# CH32F103C-R0.net
KiCad netlist of a schematic drawn in Altium Designer
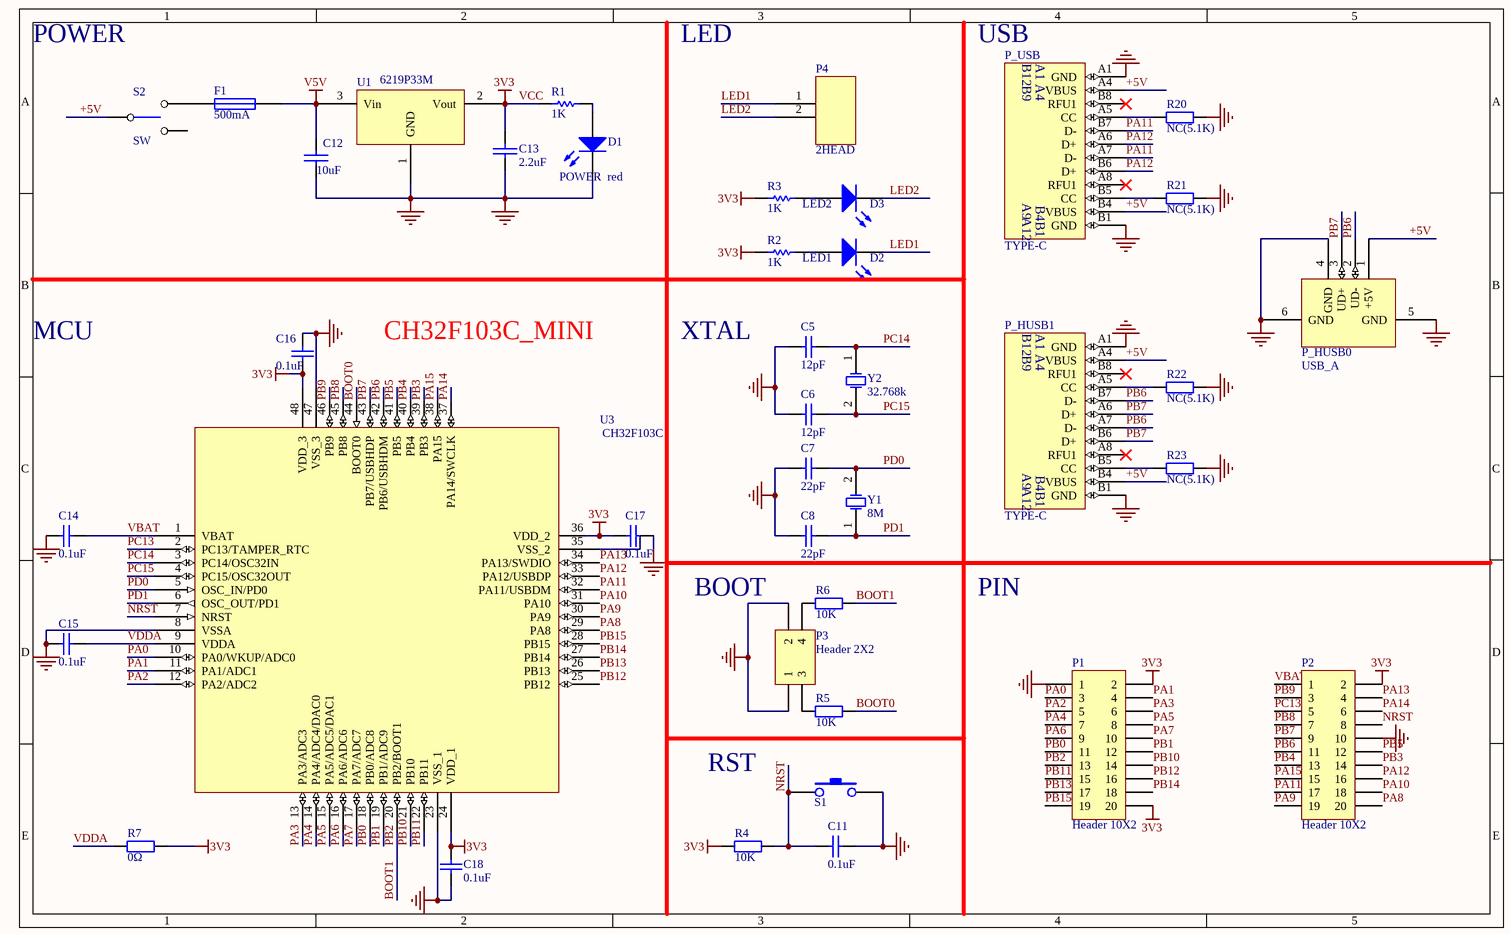
[diagram p0: CH32F103C-R0.SchDoc]

(export (version "E")
  (design (tool "Eeschema 10.0.6"))
  (components
    (comp (ref "C5")
      (value "12pF")
      (footprint "0603")
      (description "Capacitor")
      (fields (field (name "PUBLISHER") "Altium Limited"))
      (libsource (lib "*") (part "Cap"))
    )
    (comp (ref "C6")
      (value "12pF")
      (footprint "0603")
      (description "Capacitor")
      (fields (field (name "PUBLISHER") "Altium Limited"))
      (libsource (lib "*") (part "Cap"))
    )
    (comp (ref "C7")
      (value "22pF")
      (footprint "0603")
      (description "Capacitor")
      (fields (field (name "PUBLISHER") "Altium Limited"))
      (libsource (lib "*") (part "Cap"))
    )
    (comp (ref "C8")
      (value "22pF")
      (footprint "0603")
      (description "Capacitor")
      (fields (field (name "PUBLISHER") "Altium Limited"))
      (libsource (lib "*") (part "Cap"))
    )
    (comp (ref "C11")
      (value "0.1uF")
      (footprint "0603")
      (description "Capacitor")
      (fields (field (name "PUBLISHER") "Altium Limited"))
      (libsource (lib "*") (part "Cap"))
    )
    (comp (ref "C12")
      (value "10uF")
      (footprint "3216")
      (description "Capacitor")
      (libsource (lib "*") (part "CAP"))
    )
    (comp (ref "C13")
      (value "2.2uF")
      (footprint "0603")
      (description "Capacitor")
      (libsource (lib "*") (part "CAP"))
    )
    (comp (ref "C14")
      (value "0.1uF")
      (footprint "0603")
      (description "Capacitor")
      (fields (field (name "PUBLISHER") "Altium Limited"))
      (libsource (lib "*") (part "Cap"))
    )
    (comp (ref "C15")
      (value "0.1uF")
      (footprint "0603")
      (description "Capacitor")
      (fields (field (name "PUBLISHER") "Altium Limited"))
      (libsource (lib "*") (part "Cap"))
    )
    (comp (ref "C16")
      (value "0.1uF")
      (footprint "0603")
      (description "Capacitor")
      (fields (field (name "PUBLISHER") "Altium Limited"))
      (libsource (lib "*") (part "Cap"))
    )
    (comp (ref "C17")
      (value "0.1uF")
      (footprint "0603")
      (description "Capacitor")
      (fields (field (name "PUBLISHER") "Altium Limited"))
      (libsource (lib "*") (part "Cap"))
    )
    (comp (ref "C18")
      (value "0.1uF")
      (footprint "0603")
      (description "Capacitor")
      (fields (field (name "PUBLISHER") "Altium Limited"))
      (libsource (lib "*") (part "Cap"))
    )
    (comp (ref "D1")
      (value "POWER  red")
      (footprint "0603L")
      (description "Typical INFRARED GaAs LED")
      (fields (field (name "PUBLISHER") "Altium Limited"))
      (libsource (lib "*") (part "LED0"))
    )
    (comp (ref "D2")
      (value "LED1")
      (footprint "0603L")
      (description "Typical INFRARED GaAs LED")
      (fields (field (name "PUBLISHER") "Altium Limited"))
      (libsource (lib "*") (part "LED0"))
    )
    (comp (ref "D3")
      (value "LED2")
      (footprint "0603L")
      (description "Typical INFRARED GaAs LED")
      (fields (field (name "PUBLISHER") "Altium Limited"))
      (libsource (lib "*") (part "LED0"))
    )
    (comp (ref "F1")
      (value "500mA")
      (footprint "0603")
      (description "Fuse")
      (libsource (lib "*") (part "FUSE1"))
    )
    (comp (ref "P1")
      (value "Header 10X2")
      (footprint "IDC20")
      (description "Header, 10-Pin, Dual row")
      (fields (field (name "PUBLISHER") "Altium Limited"))
      (libsource (lib "*") (part "Header 10X2"))
    )
    (comp (ref "P2")
      (value "Header 10X2")
      (footprint "IDC20")
      (description "Header, 10-Pin, Dual row")
      (fields (field (name "PUBLISHER") "Altium Limited"))
      (libsource (lib "*") (part "Header 10X2"))
    )
    (comp (ref "P3")
      (value "Header 2X2")
      (footprint "HDR2X2")
      (description "Header, 2-Pin, Dual row")
      (fields (field (name "PUBLISHER") "Altium Limited"))
      (libsource (lib "*") (part "Header 2X2"))
    )
    (comp (ref "P4") (value "2HEAD") (footprint "SIP2 - 40mil") (libsource (lib "*") (part "2HEAD")))
    (comp (ref "P_HUSB0")
      (value "USB_A")
      (footprint "USBA-L")
      (description "USB Port")
      (libsource (lib "*") (part "USB"))
    )
    (comp (ref "P_HUSB1")
      (value "TYPE-C")
      (footprint "TYPE-C-Receptacle-2.0")
      (libsource (lib "*") (part "TYPE-C1"))
    )
    (comp (ref "P_USB")
      (value "TYPE-C")
      (footprint "TYPE-C-Receptacle-2.0")
      (libsource (lib "*") (part "TYPE-C1"))
    )
    (comp (ref "R1")
      (value "1K")
      (footprint "0603")
      (description "Semiconductor Resistor")
      (fields (field (name "PUBLISHER") "Altium Limited"))
      (libsource (lib "*") (part "Res Semi"))
    )
    (comp (ref "R2")
      (value "1K")
      (footprint "0603")
      (description "Semiconductor Resistor")
      (fields (field (name "PUBLISHER") "Altium Limited"))
      (libsource (lib "*") (part "Res Semi"))
    )
    (comp (ref "R3")
      (value "1K")
      (footprint "0603")
      (description "Semiconductor Resistor")
      (fields (field (name "PUBLISHER") "Altium Limited"))
      (libsource (lib "*") (part "Res Semi"))
    )
    (comp (ref "R4")
      (value "10K")
      (footprint "0603")
      (description "Resistor")
      (fields (field (name "PUBLISHER") "Altium Limited"))
      (libsource (lib "*") (part "Res2"))
    )
    (comp (ref "R5")
      (value "10K")
      (footprint "0603")
      (description "Resistor")
      (fields (field (name "PUBLISHER") "Altium Limited"))
      (libsource (lib "*") (part "Res2"))
    )
    (comp (ref "R6")
      (value "10K")
      (footprint "0603")
      (description "Resistor")
      (fields (field (name "PUBLISHER") "Altium Limited"))
      (libsource (lib "*") (part "Res2"))
    )
    (comp (ref "R7")
      (value "0Ω")
      (footprint "0603")
      (description "Resistor")
      (fields (field (name "PUBLISHER") "Altium Limited"))
      (libsource (lib "*") (part "Res2"))
    )
    (comp (ref "R20")
      (value "NC(5.1K)")
      (footprint "0603")
      (description "Resistor")
      (libsource (lib "Miscellaneous Devices") (part "Res2"))
    )
    (comp (ref "R21")
      (value "NC(5.1K)")
      (footprint "0603")
      (description "Resistor")
      (libsource (lib "Miscellaneous Devices") (part "Res2"))
    )
    (comp (ref "R22")
      (value "NC(5.1K)")
      (footprint "0603")
      (description "Resistor")
      (libsource (lib "Miscellaneous Devices") (part "Res2"))
    )
    (comp (ref "R23")
      (value "NC(5.1K)")
      (footprint "0603")
      (description "Resistor")
      (libsource (lib "Miscellaneous Devices") (part "Res2"))
    )
    (comp (ref "S1") (value "KEY") (footprint "贴片按键") (libsource (lib "*") (part "KEY")))
    (comp (ref "S2") (value "SW") (footprint "KEY2") (libsource (lib "*") (part "SW")))
    (comp (ref "U1")
      (value "6219P33M")
      (footprint "SOT-23")
      (libsource (lib "wch_sch_others") (part "6219P33M"))
    )
    (comp (ref "U3")
      (value "CH32F103C")
      (footprint "LQFP48")
      (description "ARM M3 MCU with USB device & USB host & ADC & 12bit DAC & Touch Key & CAN")
      (libsource (lib "CHXXX") (part "CH32F103C"))
    )
    (comp (ref "Y1")
      (value "8M")
      (footprint "XT62/28")
      (description "Crystal Oscillator")
      (fields (field (name "PUBLISHER") "Altium Limited"))
      (libsource (lib "*") (part "XTAL"))
    )
    (comp (ref "Y2")
      (value "32.768k")
      (footprint "FC-135")
      (description "Crystal Oscillator")
      (fields (field (name "PUBLISHER") "Altium Limited"))
      (libsource (lib "*") (part "XTAL"))
    )
  )
  (nets
    (net (code "1") (name "/+5V") (class "Default")
      (node (ref "P_HUSB0") (pin "1") (pinfunction "+5V_1") (pintype "power_in"))
      (node (ref "P_HUSB1") (pin "A4") (pinfunction "VBUS_A4") (pintype "bidirectional"))
      (node (ref "P_HUSB1") (pin "B4") (pinfunction "VBUS_B4") (pintype "bidirectional"))
      (node (ref "P_USB") (pin "A4") (pinfunction "VBUS_A4") (pintype "bidirectional"))
      (node (ref "P_USB") (pin "B4") (pinfunction "VBUS_B4") (pintype "bidirectional"))
      (node (ref "S2") (pin "1") (pinfunction "1_1") (pintype "passive"))
    )
    (net (code "3") (name "/BOOT0") (class "Default")
      (node (ref "R5") (pin "1") (pinfunction "1_1") (pintype "passive"))
      (node (ref "U3") (pin "44") (pinfunction "BOOT0_44") (pintype "input"))
    )
    (net (code "4") (name "/BOOT1") (class "Default")
      (node (ref "P1") (pin "13") (pinfunction "13_13") (pintype "passive"))
      (node (ref "R6") (pin "1") (pinfunction "1_1") (pintype "passive"))
      (node (ref "U3") (pin "20") (pinfunction "PB2/BOOT1_20") (pintype "bidirectional"))
    )
    (net (code "5") (name "/LED1") (class "Default")
      (node (ref "D2") (pin "2") (pinfunction "K_2") (pintype "passive"))
      (node (ref "P4") (pin "1") (pintype "passive"))
    )
    (net (code "6") (name "/LED2") (class "Default")
      (node (ref "D3") (pin "2") (pinfunction "K_2") (pintype "passive"))
      (node (ref "P4") (pin "2") (pintype "passive"))
    )
    (net (code "7") (name "/NRST") (class "Default")
      (node (ref "C11") (pin "2") (pinfunction "2_2") (pintype "passive"))
      (node (ref "P2") (pin "8") (pinfunction "8_8") (pintype "passive"))
      (node (ref "R4") (pin "1") (pinfunction "1_1") (pintype "passive"))
      (node (ref "S1") (pin "1") (pinfunction "1_1") (pintype "passive"))
      (node (ref "U3") (pin "7") (pinfunction "NRST_7") (pintype "input"))
    )
    (net (code "8") (name "/PA0") (class "Default")
      (node (ref "P1") (pin "3") (pinfunction "3_3") (pintype "passive"))
      (node (ref "U3") (pin "10") (pinfunction "PA0/WKUP/ADC0_10") (pintype "bidirectional"))
    )
    (net (code "9") (name "/PA1") (class "Default")
      (node (ref "P1") (pin "4") (pinfunction "4_4") (pintype "passive"))
      (node (ref "U3") (pin "11") (pinfunction "PA1/ADC1_11") (pintype "bidirectional"))
    )
    (net (code "10") (name "/PA2") (class "Default")
      (node (ref "P1") (pin "5") (pinfunction "5_5") (pintype "passive"))
      (node (ref "U3") (pin "12") (pinfunction "PA2/ADC2_12") (pintype "bidirectional"))
    )
    (net (code "11") (name "/PA3") (class "Default")
      (node (ref "P1") (pin "6") (pinfunction "6_6") (pintype "passive"))
      (node (ref "U3") (pin "13") (pinfunction "PA3/ADC3_13") (pintype "bidirectional"))
    )
    (net (code "12") (name "/PA4") (class "Default")
      (node (ref "P1") (pin "7") (pinfunction "7_7") (pintype "passive"))
      (node (ref "U3") (pin "14") (pinfunction "PA4/ADC4/DAC0_14") (pintype "bidirectional"))
    )
    (net (code "13") (name "/PA5") (class "Default")
      (node (ref "P1") (pin "8") (pinfunction "8_8") (pintype "passive"))
      (node (ref "U3") (pin "15") (pinfunction "PA5/ADC5/DAC1_15") (pintype "bidirectional"))
    )
    (net (code "14") (name "/PA6") (class "Default")
      (node (ref "P1") (pin "9") (pinfunction "9_9") (pintype "passive"))
      (node (ref "U3") (pin "16") (pinfunction "PA6/ADC6_16") (pintype "bidirectional"))
    )
    (net (code "15") (name "/PA7") (class "Default")
      (node (ref "P1") (pin "10") (pinfunction "10_10") (pintype "passive"))
      (node (ref "U3") (pin "17") (pinfunction "PA7/ADC7_17") (pintype "bidirectional"))
    )
    (net (code "16") (name "/PA8") (class "Default")
      (node (ref "P2") (pin "20") (pinfunction "20_20") (pintype "passive"))
      (node (ref "U3") (pin "29") (pinfunction "PA8_29") (pintype "bidirectional"))
    )
    (net (code "17") (name "/PA9") (class "Default")
      (node (ref "P2") (pin "19") (pinfunction "19_19") (pintype "passive"))
      (node (ref "U3") (pin "30") (pinfunction "PA9_30") (pintype "bidirectional"))
    )
    (net (code "18") (name "/PA10") (class "Default")
      (node (ref "P2") (pin "18") (pinfunction "18_18") (pintype "passive"))
      (node (ref "U3") (pin "31") (pinfunction "PA10_31") (pintype "bidirectional"))
    )
    (net (code "19") (name "/PA11") (class "Default")
      (node (ref "P2") (pin "17") (pinfunction "17_17") (pintype "passive"))
      (node (ref "P_USB") (pin "A7") (pinfunction "D-_A7") (pintype "bidirectional"))
      (node (ref "P_USB") (pin "B7") (pinfunction "D-_B7") (pintype "bidirectional"))
      (node (ref "U3") (pin "32") (pinfunction "PA11/USBDM_32") (pintype "bidirectional"))
    )
    (net (code "20") (name "/PA12") (class "Default")
      (node (ref "P2") (pin "16") (pinfunction "16_16") (pintype "passive"))
      (node (ref "P_USB") (pin "A6") (pinfunction "D+_A6") (pintype "bidirectional"))
      (node (ref "P_USB") (pin "B6") (pinfunction "D+_B6") (pintype "bidirectional"))
      (node (ref "U3") (pin "33") (pinfunction "PA12/USBDP_33") (pintype "bidirectional"))
    )
    (net (code "21") (name "/PA13") (class "Default")
      (node (ref "P2") (pin "4") (pinfunction "4_4") (pintype "passive"))
      (node (ref "U3") (pin "34") (pinfunction "PA13/SWDIO_34") (pintype "bidirectional"))
    )
    (net (code "22") (name "/PA14") (class "Default")
      (node (ref "P2") (pin "6") (pinfunction "6_6") (pintype "passive"))
      (node (ref "U3") (pin "37") (pinfunction "PA14/SWCLK_37") (pintype "bidirectional"))
    )
    (net (code "23") (name "/PA15") (class "Default")
      (node (ref "P2") (pin "15") (pinfunction "15_15") (pintype "passive"))
      (node (ref "U3") (pin "38") (pinfunction "PA15_38") (pintype "bidirectional"))
    )
    (net (code "24") (name "/PB0") (class "Default")
      (node (ref "P1") (pin "11") (pinfunction "11_11") (pintype "passive"))
      (node (ref "U3") (pin "18") (pinfunction "PB0/ADC8_18") (pintype "bidirectional"))
    )
    (net (code "25") (name "/PB1") (class "Default")
      (node (ref "P1") (pin "12") (pinfunction "12_12") (pintype "passive"))
      (node (ref "U3") (pin "19") (pinfunction "PB1/ADC9_19") (pintype "bidirectional"))
    )
    (net (code "26") (name "/PB3") (class "Default")
      (node (ref "P2") (pin "14") (pinfunction "14_14") (pintype "passive"))
      (node (ref "U3") (pin "39") (pinfunction "PB3_39") (pintype "bidirectional"))
    )
    (net (code "27") (name "/PB4") (class "Default")
      (node (ref "P2") (pin "13") (pinfunction "13_13") (pintype "passive"))
      (node (ref "U3") (pin "40") (pinfunction "PB4_40") (pintype "bidirectional"))
    )
    (net (code "28") (name "/PB5") (class "Default")
      (node (ref "P2") (pin "12") (pinfunction "12_12") (pintype "passive"))
      (node (ref "U3") (pin "41") (pinfunction "PB5_41") (pintype "bidirectional"))
    )
    (net (code "29") (name "/PB6") (class "Default")
      (node (ref "P2") (pin "11") (pinfunction "11_11") (pintype "passive"))
      (node (ref "P_HUSB0") (pin "2") (pinfunction "UD-_2") (pintype "bidirectional"))
      (node (ref "P_HUSB1") (pin "A7") (pinfunction "D-_A7") (pintype "bidirectional"))
      (node (ref "P_HUSB1") (pin "B7") (pinfunction "D-_B7") (pintype "bidirectional"))
      (node (ref "U3") (pin "42") (pinfunction "PB6/USBHDM_42") (pintype "bidirectional"))
    )
    (net (code "30") (name "/PB7") (class "Default")
      (node (ref "P2") (pin "9") (pinfunction "9_9") (pintype "passive"))
      (node (ref "P_HUSB0") (pin "3") (pinfunction "UD+_3") (pintype "bidirectional"))
      (node (ref "P_HUSB1") (pin "A6") (pinfunction "D+_A6") (pintype "bidirectional"))
      (node (ref "P_HUSB1") (pin "B6") (pinfunction "D+_B6") (pintype "bidirectional"))
      (node (ref "U3") (pin "43") (pinfunction "PB7/USBHDP_43") (pintype "bidirectional"))
    )
    (net (code "31") (name "/PB8") (class "Default")
      (node (ref "P2") (pin "7") (pinfunction "7_7") (pintype "passive"))
      (node (ref "U3") (pin "45") (pinfunction "PB8_45") (pintype "bidirectional"))
    )
    (net (code "32") (name "/PB9") (class "Default")
      (node (ref "P2") (pin "3") (pinfunction "3_3") (pintype "passive"))
      (node (ref "U3") (pin "46") (pinfunction "PB9_46") (pintype "bidirectional"))
    )
    (net (code "33") (name "/PB10") (class "Default")
      (node (ref "P1") (pin "14") (pinfunction "14_14") (pintype "passive"))
      (node (ref "U3") (pin "21") (pinfunction "PB10_21") (pintype "bidirectional"))
    )
    (net (code "34") (name "/PB11") (class "Default")
      (node (ref "P1") (pin "15") (pinfunction "15_15") (pintype "passive"))
      (node (ref "U3") (pin "22") (pinfunction "PB11_22") (pintype "bidirectional"))
    )
    (net (code "35") (name "/PB12") (class "Default")
      (node (ref "P1") (pin "16") (pinfunction "16_16") (pintype "passive"))
      (node (ref "U3") (pin "25") (pinfunction "PB12_25") (pintype "bidirectional"))
    )
    (net (code "36") (name "/PB13") (class "Default")
      (node (ref "P1") (pin "17") (pinfunction "17_17") (pintype "passive"))
      (node (ref "U3") (pin "26") (pinfunction "PB13_26") (pintype "bidirectional"))
    )
    (net (code "37") (name "/PB14") (class "Default")
      (node (ref "P1") (pin "18") (pinfunction "18_18") (pintype "passive"))
      (node (ref "U3") (pin "27") (pinfunction "PB14_27") (pintype "bidirectional"))
    )
    (net (code "38") (name "/PB15") (class "Default")
      (node (ref "P1") (pin "19") (pinfunction "19_19") (pintype "passive"))
      (node (ref "U3") (pin "28") (pinfunction "PB15_28") (pintype "bidirectional"))
    )
    (net (code "39") (name "/PC13") (class "Default")
      (node (ref "P2") (pin "5") (pinfunction "5_5") (pintype "passive"))
      (node (ref "U3") (pin "2") (pinfunction "PC13/TAMPER_RTC_2") (pintype "bidirectional"))
    )
    (net (code "40") (name "/PC14") (class "Default")
      (node (ref "C5") (pin "1") (pinfunction "1_1") (pintype "passive"))
      (node (ref "U3") (pin "3") (pinfunction "PC14/OSC32IN_3") (pintype "bidirectional"))
      (node (ref "Y2") (pin "1") (pinfunction "OSC1_1") (pintype "passive"))
    )
    (net (code "41") (name "/PC15") (class "Default")
      (node (ref "C6") (pin "1") (pinfunction "1_1") (pintype "passive"))
      (node (ref "U3") (pin "4") (pinfunction "PC15/OSC32OUT_4") (pintype "bidirectional"))
      (node (ref "Y2") (pin "2") (pinfunction "OSC2_2") (pintype "passive"))
    )
    (net (code "42") (name "/PD0") (class "Default")
      (node (ref "C7") (pin "2") (pinfunction "2_2") (pintype "passive"))
      (node (ref "U3") (pin "5") (pinfunction "OSC_IN/PD0_5") (pintype "input"))
      (node (ref "Y1") (pin "2") (pinfunction "OSC2_2") (pintype "passive"))
    )
    (net (code "43") (name "/PD1") (class "Default")
      (node (ref "C8") (pin "2") (pinfunction "2_2") (pintype "passive"))
      (node (ref "U3") (pin "6") (pinfunction "OSC_OUT/PD1_6") (pintype "output"))
      (node (ref "Y1") (pin "1") (pinfunction "OSC1_1") (pintype "passive"))
    )
    (net (code "44") (name "/VBAT") (class "Default")
      (node (ref "C14") (pin "1") (pinfunction "1_1") (pintype "passive"))
      (node (ref "P2") (pin "1") (pinfunction "1_1") (pintype "passive"))
      (node (ref "U3") (pin "1") (pinfunction "VBAT_1") (pintype "power_in"))
    )
    (net (code "45") (name "/VDDA") (class "Default")
      (node (ref "C15") (pin "1") (pinfunction "1_1") (pintype "passive"))
      (node (ref "R7") (pin "2") (pinfunction "2_2") (pintype "passive"))
      (node (ref "U3") (pin "9") (pinfunction "VDDA_9") (pintype "power_in"))
    )
    (net (code "46") (name "3V3") (class "Default")
      (node (ref "C13") (pin "1") (pinfunction "1_1") (pintype "passive"))
      (node (ref "C16") (pin "2") (pinfunction "2_2") (pintype "passive"))
      (node (ref "C17") (pin "2") (pinfunction "2_2") (pintype "passive"))
      (node (ref "C18") (pin "2") (pinfunction "2_2") (pintype "passive"))
      (node (ref "P1") (pin "2") (pinfunction "2_2") (pintype "passive"))
      (node (ref "P1") (pin "20") (pinfunction "20_20") (pintype "passive"))
      (node (ref "P2") (pin "2") (pinfunction "2_2") (pintype "passive"))
      (node (ref "R1") (pin "2") (pinfunction "2_2") (pintype "passive"))
      (node (ref "R2") (pin "1") (pinfunction "1_1") (pintype "passive"))
      (node (ref "R3") (pin "1") (pinfunction "1_1") (pintype "passive"))
      (node (ref "R4") (pin "2") (pinfunction "2_2") (pintype "passive"))
      (node (ref "R7") (pin "1") (pinfunction "1_1") (pintype "passive"))
      (node (ref "U1") (pin "2") (pinfunction "Vout_2") (pintype "passive"))
      (node (ref "U3") (pin "24") (pinfunction "VDD_1_24") (pintype "power_in"))
      (node (ref "U3") (pin "36") (pinfunction "VDD_2_36") (pintype "power_in"))
      (node (ref "U3") (pin "48") (pinfunction "VDD_3_48") (pintype "power_in"))
    )
    (net (code "47") (name "GND") (class "Default")
      (node (ref "C11") (pin "1") (pinfunction "1_1") (pintype "passive"))
      (node (ref "C12") (pin "2") (pinfunction "2_2") (pintype "passive"))
      (node (ref "C13") (pin "2") (pinfunction "2_2") (pintype "passive"))
      (node (ref "C14") (pin "2") (pinfunction "2_2") (pintype "passive"))
      (node (ref "C15") (pin "2") (pinfunction "2_2") (pintype "passive"))
      (node (ref "C16") (pin "1") (pinfunction "1_1") (pintype "passive"))
      (node (ref "C17") (pin "1") (pinfunction "1_1") (pintype "passive"))
      (node (ref "C18") (pin "1") (pinfunction "1_1") (pintype "passive"))
      (node (ref "C5") (pin "2") (pinfunction "2_2") (pintype "passive"))
      (node (ref "C6") (pin "2") (pinfunction "2_2") (pintype "passive"))
      (node (ref "C7") (pin "1") (pinfunction "1_1") (pintype "passive"))
      (node (ref "C8") (pin "1") (pinfunction "1_1") (pintype "passive"))
      (node (ref "D1") (pin "2") (pinfunction "K_2") (pintype "passive"))
      (node (ref "P1") (pin "1") (pinfunction "1_1") (pintype "passive"))
      (node (ref "P2") (pin "10") (pinfunction "10_10") (pintype "passive"))
      (node (ref "P3") (pin "1") (pinfunction "1_1") (pintype "passive"))
      (node (ref "P3") (pin "2") (pinfunction "2_2") (pintype "passive"))
      (node (ref "P_HUSB0") (pin "4") (pinfunction "GND_4") (pintype "power_in"))
      (node (ref "P_HUSB0") (pin "5") (pinfunction "GND_5") (pintype "power_in"))
      (node (ref "P_HUSB0") (pin "6") (pinfunction "GND_6") (pintype "power_in"))
      (node (ref "P_HUSB1") (pin "A1") (pinfunction "GND_A1") (pintype "bidirectional"))
      (node (ref "P_HUSB1") (pin "B1") (pinfunction "GND_B1") (pintype "bidirectional"))
      (node (ref "P_USB") (pin "A1") (pinfunction "GND_A1") (pintype "bidirectional"))
      (node (ref "P_USB") (pin "B1") (pinfunction "GND_B1") (pintype "bidirectional"))
      (node (ref "R20") (pin "2") (pinfunction "2_2") (pintype "passive"))
      (node (ref "R21") (pin "2") (pinfunction "2_2") (pintype "passive"))
      (node (ref "R22") (pin "2") (pinfunction "2_2") (pintype "passive"))
      (node (ref "R23") (pin "2") (pinfunction "2_2") (pintype "passive"))
      (node (ref "S1") (pin "3") (pinfunction "3_3") (pintype "passive"))
      (node (ref "U1") (pin "1") (pinfunction "GND_1") (pintype "passive"))
      (node (ref "U3") (pin "23") (pinfunction "VSS_1_23") (pintype "power_in"))
      (node (ref "U3") (pin "47") (pinfunction "VSS_3_47") (pintype "power_in"))
      (node (ref "U3") (pin "8") (pinfunction "VSSA_8") (pintype "power_in"))
    )
    (net (code "48") (name "Net-(D1-A)") (class "Default")
      (node (ref "D1") (pin "1") (pinfunction "A_1") (pintype "passive"))
      (node (ref "R1") (pin "1") (pinfunction "1_1") (pintype "passive"))
    )
    (net (code "49") (name "Net-(D2-A)") (class "Default")
      (node (ref "D2") (pin "1") (pinfunction "A_1") (pintype "passive"))
      (node (ref "R2") (pin "2") (pinfunction "2_2") (pintype "passive"))
    )
    (net (code "50") (name "Net-(D3-A)") (class "Default")
      (node (ref "D3") (pin "1") (pinfunction "A_1") (pintype "passive"))
      (node (ref "R3") (pin "2") (pinfunction "2_2") (pintype "passive"))
    )
    (net (code "51") (name "Net-(F1-Pad1)") (class "Default")
      (node (ref "F1") (pin "1") (pinfunction "1_1") (pintype "passive"))
      (node (ref "S2") (pin "3") (pinfunction "3_3") (pintype "passive"))
    )
    (net (code "52") (name "Net-(P3-Pad3)") (class "Default")
      (node (ref "P3") (pin "3") (pinfunction "3_3") (pintype "passive"))
      (node (ref "R5") (pin "2") (pinfunction "2_2") (pintype "passive"))
    )
    (net (code "53") (name "Net-(P3-Pad4)") (class "Default")
      (node (ref "P3") (pin "4") (pinfunction "4_4") (pintype "passive"))
      (node (ref "R6") (pin "2") (pinfunction "2_2") (pintype "passive"))
    )
    (net (code "54") (name "Net-(P_HUSB1-CC-PadA5)") (class "Default")
      (node (ref "P_HUSB1") (pin "A5") (pinfunction "CC_A5") (pintype "bidirectional"))
      (node (ref "R22") (pin "1") (pinfunction "1_1") (pintype "passive"))
    )
    (net (code "55") (name "Net-(P_HUSB1-CC-PadB5)") (class "Default")
      (node (ref "P_HUSB1") (pin "B5") (pinfunction "CC_B5") (pintype "bidirectional"))
      (node (ref "R23") (pin "1") (pinfunction "1_1") (pintype "passive"))
    )
    (net (code "56") (name "Net-(P_USB-CC-PadA5)") (class "Default")
      (node (ref "P_USB") (pin "A5") (pinfunction "CC_A5") (pintype "bidirectional"))
      (node (ref "R20") (pin "1") (pinfunction "1_1") (pintype "passive"))
    )
    (net (code "57") (name "Net-(P_USB-CC-PadB5)") (class "Default")
      (node (ref "P_USB") (pin "B5") (pinfunction "CC_B5") (pintype "bidirectional"))
      (node (ref "R21") (pin "1") (pinfunction "1_1") (pintype "passive"))
    )
    (net (code "58") (name "V5V") (class "Default")
      (node (ref "C12") (pin "1") (pinfunction "1_1") (pintype "passive"))
      (node (ref "F1") (pin "2") (pinfunction "2_2") (pintype "passive"))
      (node (ref "U1") (pin "3") (pinfunction "Vin_3") (pintype "passive"))
    )
    (net (code "59") (name "unconnected-(P_HUSB1-RFU1-PadA8)") (class "Default")
      (node (ref "P_HUSB1") (pin "A8") (pinfunction "RFU1_A8") (pintype "bidirectional+no_connect"))
    )
    (net (code "60") (name "unconnected-(P_HUSB1-RFU1-PadB8)") (class "Default")
      (node (ref "P_HUSB1") (pin "B8") (pinfunction "RFU1_B8") (pintype "bidirectional+no_connect"))
    )
    (net (code "61") (name "unconnected-(P_USB-RFU1-PadA8)") (class "Default")
      (node (ref "P_USB") (pin "A8") (pinfunction "RFU1_A8") (pintype "bidirectional+no_connect"))
    )
    (net (code "62") (name "unconnected-(P_USB-RFU1-PadB8)") (class "Default")
      (node (ref "P_USB") (pin "B8") (pinfunction "RFU1_B8") (pintype "bidirectional+no_connect"))
    )
    (net (code "63") (name "unconnected-(S2-Pad2)") (class "Default")
      (node (ref "S2") (pin "2") (pinfunction "2_2") (pintype "passive"))
    )
    (net (code "64") (name "unconnected-(U3-VSS_2-Pad35)") (class "Default")
      (node (ref "U3") (pin "35") (pinfunction "VSS_2_35") (pintype "power_in"))
    )
  )
)
